# STCLock.net
KiCad netlist of a schematic drawn in Altium Designer
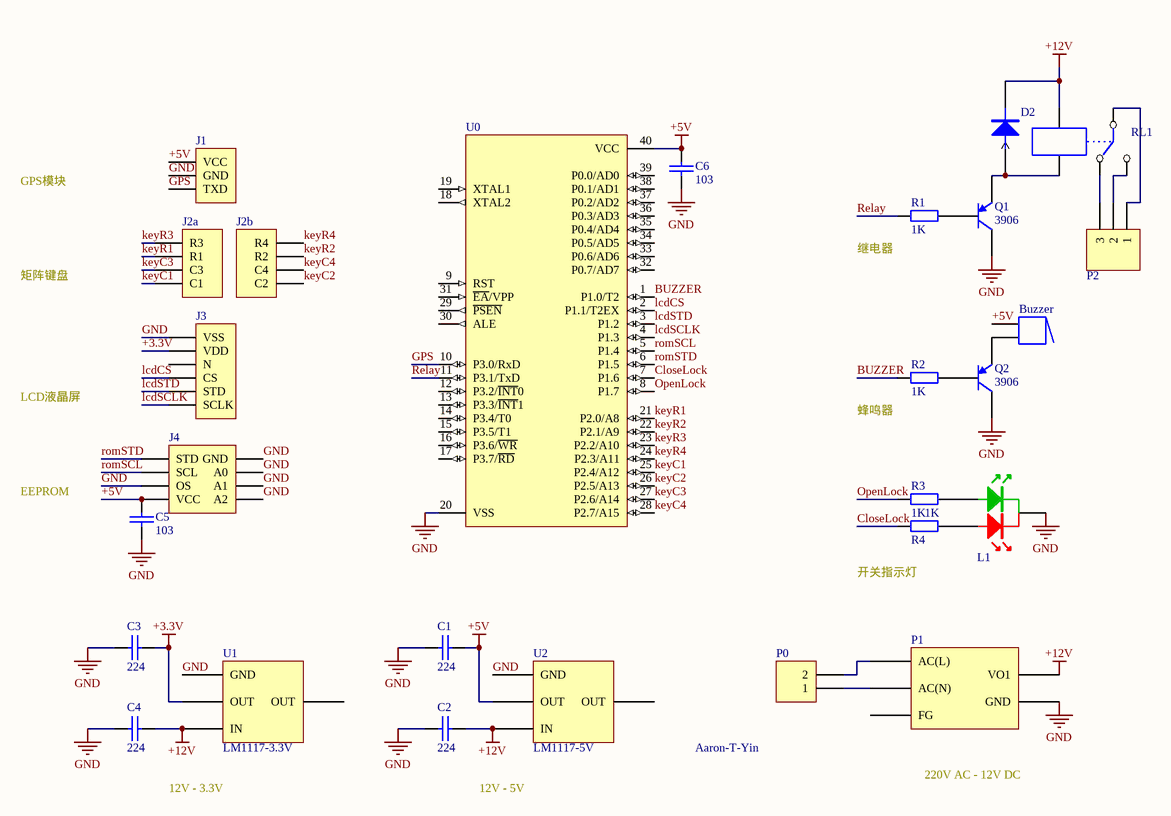
[diagram p0: STCLock.SchDoc]

(export (version "E")
  (design (tool "Eeschema 10.0.6"))
  (components
    (comp (ref "*") (value "AaronTYin") (libsource (lib "ET_SCHLIB") (part "AaronTYin")))
    (comp (ref "Buzzer")
      (value "Buzzer")
      (footprint "BUZ8/12")
      (description "Magnetic Transducer Buzzer")
      (fields (field (name "PUBLISHER") "Altium Limited"))
      (libsource (lib "Miscellaneous Devices") (part "Buzzer"))
    )
    (comp (ref "C1")
      (value "224")
      (footprint "0805")
      (description "Capacitor")
      (libsource (lib "ET_SCHLIB") (part "CAP"))
    )
    (comp (ref "C2")
      (value "224")
      (footprint "0805")
      (description "Capacitor")
      (libsource (lib "ET_SCHLIB") (part "CAP"))
    )
    (comp (ref "C3")
      (value "224")
      (footprint "0805")
      (description "Capacitor")
      (libsource (lib "ET_SCHLIB") (part "CAP"))
    )
    (comp (ref "C4")
      (value "224")
      (footprint "0805")
      (description "Capacitor")
      (libsource (lib "ET_SCHLIB") (part "CAP"))
    )
    (comp (ref "C5")
      (value "103")
      (footprint "0805")
      (description "Capacitor")
      (libsource (lib "ET_SCHLIB") (part "CAP"))
    )
    (comp (ref "C6")
      (value "103")
      (footprint "0805")
      (description "Capacitor")
      (libsource (lib "ET_SCHLIB") (part "CAP"))
    )
    (comp (ref "D2")
      (value "DIODE")
      (footprint "5819")
      (description "Diode")
      (libsource (lib "ET_SCHLIB") (part "DIODE"))
    )
    (comp (ref "J1")
      (value "GPS")
      (footprint "HDR1X3")
      (description "Header, 3-Pin")
      (fields (field (name "PUBLISHER") "Altium Limited"))
      (libsource (lib "") (part "Header 3_1"))
    )
    (comp (ref "J2a")
      (value "Header 4")
      (footprint "HDR1X4")
      (description "Header, 4-Pin")
      (fields (field (name "PUBLISHER") "Altium Limited"))
      (libsource (lib "Miscellaneous Connectors") (part "Header 4"))
    )
    (comp (ref "J2b")
      (value "Header 4")
      (footprint "HDR1X4")
      (description "Header, 4-Pin")
      (fields (field (name "PUBLISHER") "Altium Limited"))
      (libsource (lib "") (part "Header 4_1"))
    )
    (comp (ref "J3")
      (value "LCD12864")
      (footprint "HDR1X6")
      (description "Header, 6-Pin")
      (fields (field (name "PUBLISHER") "Altium Limited"))
      (libsource (lib "Miscellaneous Connectors") (part "Header 6"))
    )
    (comp (ref "J4") (value "AT24C02") (footprint "DIP8") (libsource (lib "ET_SCHLIB") (part "LM75A")))
    (comp (ref "L1") (value "LED_3_K") (footprint "HDR1X3") (libsource (lib "ET_SCHLIB") (part "LED_3_K")))
    (comp (ref "P0")
      (value "Header 2")
      (footprint "DG46G_2")
      (description "Header, 2-Pin")
      (fields (field (name "PUBLISHER") "Altium Limited"))
      (libsource (lib "Miscellaneous Connectors") (part "Header 2"))
    )
    (comp (ref "P1")
      (value "LAP5-220SXX")
      (footprint "LAP5-220SXX")
      (libsource (lib "ET_SCHLIB") (part "LAP5-220SXX"))
    )
    (comp (ref "P2")
      (value "Header 3")
      (footprint "111")
      (description "Header, 3-Pin")
      (fields (field (name "PUBLISHER") "Altium Limited"))
      (libsource (lib "Miscellaneous Connectors") (part "Header 3"))
    )
    (comp (ref "Q1")
      (value "3906")
      (footprint "SOT-23-et")
      (description "PNP General Purpose Amplifier")
      (fields (field (name "PUBLISHER") "Altium Limited"))
      (libsource (lib "Miscellaneous Devices") (part "2N3906"))
    )
    (comp (ref "Q2")
      (value "3906")
      (footprint "SOT-23-et")
      (description "PNP General Purpose Amplifier")
      (fields (field (name "PUBLISHER") "Altium Limited"))
      (libsource (lib "Miscellaneous Devices") (part "2N3906"))
    )
    (comp (ref "R1")
      (value "1K")
      (footprint "0805")
      (description "Semiconductor Resistor")
      (fields (field (name "Comment") "Res Semi") (field (name "PUBLISHER") "Altium Limited"))
      (libsource (lib "Miscellaneous Devices") (part "Res Semi"))
    )
    (comp (ref "R2")
      (value "1K")
      (footprint "0805")
      (description "Semiconductor Resistor")
      (fields (field (name "Comment") "Res Semi") (field (name "PUBLISHER") "Altium Limited"))
      (libsource (lib "Miscellaneous Devices") (part "Res Semi"))
    )
    (comp (ref "R3")
      (value "1K")
      (footprint "0805")
      (description "Resistor")
      (fields (field (name "Comment") "Res2") (field (name "PUBLISHER") "Altium Limited"))
      (libsource (lib "Miscellaneous Devices") (part "Res2"))
    )
    (comp (ref "R4")
      (value "1K")
      (footprint "0805")
      (description "Resistor")
      (fields (field (name "Comment") "Res2") (field (name "PUBLISHER") "Altium Limited"))
      (libsource (lib "Miscellaneous Devices") (part "Res2"))
    )
    (comp (ref "RL1") (value "G2R-1") (footprint "G2R-1") (libsource (lib "ET_SCHLIB") (part "G2R-1")))
    (comp (ref "U0")
      (value "STC89C52RC")
      (footprint "SOT129-1")
      (description "80C51 8-Bit Flash Microcontroller Family, 4 kB Flash")
      (fields (field (name "PUBLISHER") "Altium Limited"))
      (libsource (lib "Philips Microcontroller 8-Bit") (part "P89C51X2BN"))
    )
    (comp (ref "U1")
      (value "LM1117-3.3V")
      (footprint "AMS1117")
      (libsource (lib "ET_SCHLIB") (part "LM1117"))
    )
    (comp (ref "U2") (value "LM1117-5V") (footprint "AMS1117") (libsource (lib "ET_SCHLIB") (part "LM1117")))
  )
  (nets
    (net (code "1") (name "+3.3V") (class "Default")
      (node (ref "C3") (pin "2") (pintype "passive"))
      (node (ref "J3") (pin "2") (pinfunction "VDD_2") (pintype "passive"))
      (node (ref "U1") (pin "2") (pinfunction "OUT_2") (pintype "passive"))
    )
    (net (code "2") (name "+5V") (class "Default")
      (node (ref "Buzzer") (pin "1") (pinfunction "1_1") (pintype "passive"))
      (node (ref "C1") (pin "2") (pintype "passive"))
      (node (ref "C5") (pin "1") (pintype "passive"))
      (node (ref "C6") (pin "1") (pintype "passive"))
      (node (ref "J1") (pin "1") (pinfunction "VCC_1") (pintype "passive"))
      (node (ref "J4") (pin "4") (pinfunction "VCC_4") (pintype "passive"))
      (node (ref "U0") (pin "40") (pinfunction "VCC_40") (pintype "power_in"))
      (node (ref "U2") (pin "2") (pinfunction "OUT_2") (pintype "passive"))
    )
    (net (code "3") (name "+12V") (class "Default")
      (node (ref "C2") (pin "2") (pintype "passive"))
      (node (ref "C4") (pin "2") (pintype "passive"))
      (node (ref "D2") (pin "2") (pintype "passive"))
      (node (ref "P1") (pin "4") (pinfunction "VO1_4") (pintype "passive"))
      (node (ref "RL1") (pin "5") (pintype "passive"))
      (node (ref "U1") (pin "3") (pinfunction "IN_3") (pintype "passive"))
      (node (ref "U2") (pin "3") (pinfunction "IN_3") (pintype "passive"))
    )
    (net (code "4") (name "/BUZZER") (class "Default")
      (node (ref "R2") (pin "1") (pinfunction "1_1") (pintype "passive"))
      (node (ref "U0") (pin "1") (pinfunction "P1.0/T2_1") (pintype "bidirectional"))
    )
    (net (code "5") (name "/CloseLock") (class "Default")
      (node (ref "R4") (pin "1") (pinfunction "1_1") (pintype "passive"))
      (node (ref "U0") (pin "7") (pinfunction "P1.6_7") (pintype "bidirectional"))
    )
    (net (code "6") (name "/GPS") (class "Default")
      (node (ref "J1") (pin "3") (pinfunction "TXD_3") (pintype "passive"))
      (node (ref "U0") (pin "10") (pinfunction "P3.0/RxD_10") (pintype "bidirectional"))
    )
    (net (code "7") (name "/OpenLock") (class "Default")
      (node (ref "R3") (pin "1") (pinfunction "1_1") (pintype "passive"))
      (node (ref "U0") (pin "8") (pinfunction "P1.7_8") (pintype "bidirectional"))
    )
    (net (code "8") (name "/Relay") (class "Default")
      (node (ref "R1") (pin "1") (pinfunction "1_1") (pintype "passive"))
      (node (ref "U0") (pin "11") (pinfunction "P3.1/TxD_11") (pintype "bidirectional"))
    )
    (net (code "9") (name "/keyC1") (class "Default")
      (node (ref "J2a") (pin "4") (pinfunction "C1_4") (pintype "passive"))
      (node (ref "U0") (pin "25") (pinfunction "P2.4/A12_25") (pintype "bidirectional"))
    )
    (net (code "10") (name "/keyC2") (class "Default")
      (node (ref "J2b") (pin "1") (pinfunction "C2_1") (pintype "passive"))
      (node (ref "U0") (pin "26") (pinfunction "P2.5/A13_26") (pintype "bidirectional"))
    )
    (net (code "11") (name "/keyC3") (class "Default")
      (node (ref "J2a") (pin "3") (pinfunction "C3_3") (pintype "passive"))
      (node (ref "U0") (pin "27") (pinfunction "P2.6/A14_27") (pintype "bidirectional"))
    )
    (net (code "12") (name "/keyC4") (class "Default")
      (node (ref "J2b") (pin "2") (pinfunction "C4_2") (pintype "passive"))
      (node (ref "U0") (pin "28") (pinfunction "P2.7/A15_28") (pintype "bidirectional"))
    )
    (net (code "13") (name "/keyR1") (class "Default")
      (node (ref "J2a") (pin "2") (pinfunction "R1_2") (pintype "passive"))
      (node (ref "U0") (pin "21") (pinfunction "P2.0/A8_21") (pintype "bidirectional"))
    )
    (net (code "14") (name "/keyR2") (class "Default")
      (node (ref "J2b") (pin "3") (pinfunction "R2_3") (pintype "passive"))
      (node (ref "U0") (pin "22") (pinfunction "P2.1/A9_22") (pintype "bidirectional"))
    )
    (net (code "15") (name "/keyR3") (class "Default")
      (node (ref "J2a") (pin "1") (pinfunction "R3_1") (pintype "passive"))
      (node (ref "U0") (pin "23") (pinfunction "P2.2/A10_23") (pintype "bidirectional"))
    )
    (net (code "16") (name "/keyR4") (class "Default")
      (node (ref "J2b") (pin "4") (pinfunction "R4_4") (pintype "passive"))
      (node (ref "U0") (pin "24") (pinfunction "P2.3/A11_24") (pintype "bidirectional"))
    )
    (net (code "17") (name "/lcdCS") (class "Default")
      (node (ref "J3") (pin "4") (pinfunction "CS_4") (pintype "passive"))
      (node (ref "U0") (pin "2") (pinfunction "P1.1/T2EX_2") (pintype "bidirectional"))
    )
    (net (code "18") (name "/lcdSCLK") (class "Default")
      (node (ref "J3") (pin "6") (pinfunction "SCLK_6") (pintype "passive"))
      (node (ref "U0") (pin "4") (pinfunction "P1.3_4") (pintype "bidirectional"))
    )
    (net (code "19") (name "/lcdSTD") (class "Default")
      (node (ref "J3") (pin "5") (pinfunction "STD_5") (pintype "passive"))
      (node (ref "U0") (pin "3") (pinfunction "P1.2_3") (pintype "bidirectional"))
    )
    (net (code "20") (name "/romSCL") (class "Default")
      (node (ref "J4") (pin "2") (pinfunction "SCL_2") (pintype "passive"))
      (node (ref "U0") (pin "5") (pinfunction "P1.4_5") (pintype "bidirectional"))
    )
    (net (code "21") (name "/romSTD") (class "Default")
      (node (ref "J4") (pin "1") (pinfunction "STD_1") (pintype "passive"))
      (node (ref "U0") (pin "6") (pinfunction "P1.5_6") (pintype "bidirectional"))
    )
    (net (code "22") (name "GND") (class "Default")
      (node (ref "C1") (pin "1") (pintype "passive"))
      (node (ref "C2") (pin "1") (pintype "passive"))
      (node (ref "C3") (pin "1") (pintype "passive"))
      (node (ref "C4") (pin "1") (pintype "passive"))
      (node (ref "C5") (pin "2") (pintype "passive"))
      (node (ref "C6") (pin "2") (pintype "passive"))
      (node (ref "J1") (pin "2") (pinfunction "GND_2") (pintype "passive"))
      (node (ref "J3") (pin "1") (pinfunction "VSS_1") (pintype "passive"))
      (node (ref "J4") (pin "3") (pinfunction "OS_3") (pintype "passive"))
      (node (ref "J4") (pin "5") (pinfunction "A2_5") (pintype "passive"))
      (node (ref "J4") (pin "6") (pinfunction "A1_6") (pintype "passive"))
      (node (ref "J4") (pin "7") (pinfunction "A0_7") (pintype "passive"))
      (node (ref "J4") (pin "8") (pinfunction "GND_8") (pintype "passive"))
      (node (ref "L1") (pin "1") (pintype "passive"))
      (node (ref "P1") (pin "5") (pinfunction "GND_5") (pintype "passive"))
      (node (ref "Q1") (pin "3") (pinfunction "C_3") (pintype "passive"))
      (node (ref "Q2") (pin "3") (pinfunction "C_3") (pintype "passive"))
      (node (ref "U0") (pin "20") (pinfunction "VSS_20") (pintype "power_in"))
      (node (ref "U1") (pin "1") (pinfunction "GND_1") (pintype "passive"))
      (node (ref "U2") (pin "1") (pinfunction "GND_1") (pintype "passive"))
    )
    (net (code "23") (name "Net-(L1-Pad2)") (class "Default")
      (node (ref "L1") (pin "2") (pintype "passive"))
      (node (ref "R4") (pin "2") (pinfunction "2_2") (pintype "passive"))
    )
    (net (code "24") (name "Net-(L1-Pad3)") (class "Default")
      (node (ref "L1") (pin "3") (pintype "passive"))
      (node (ref "R3") (pin "2") (pinfunction "2_2") (pintype "passive"))
    )
    (net (code "25") (name "Net-(P1-AC(L))") (class "Default")
      (node (ref "P0") (pin "2") (pinfunction "2_2") (pintype "passive"))
      (node (ref "P1") (pin "3") (pinfunction "AC(L)_3") (pintype "passive"))
    )
    (net (code "26") (name "Net-(P1-AC(N))") (class "Default")
      (node (ref "P0") (pin "1") (pinfunction "1_1") (pintype "passive"))
      (node (ref "P1") (pin "2") (pinfunction "AC(N)_2") (pintype "passive"))
    )
    (net (code "27") (name "Net-(P2-Pad1)") (class "Default")
      (node (ref "P2") (pin "1") (pinfunction "1_1") (pintype "passive"))
      (node (ref "RL1") (pin "4") (pintype "passive"))
    )
    (net (code "28") (name "Net-(P2-Pad2)") (class "Default")
      (node (ref "P2") (pin "2") (pinfunction "2_2") (pintype "passive"))
      (node (ref "RL1") (pin "3") (pintype "passive"))
    )
    (net (code "29") (name "Net-(P2-Pad3)") (class "Default")
      (node (ref "P2") (pin "3") (pinfunction "3_3") (pintype "passive"))
      (node (ref "RL1") (pin "2") (pintype "passive"))
    )
    (net (code "30") (name "Net-(Q1-B)") (class "Default")
      (node (ref "Q1") (pin "2") (pinfunction "B_2") (pintype "passive"))
      (node (ref "R1") (pin "2") (pinfunction "2_2") (pintype "passive"))
    )
    (net (code "31") (name "Net-(Q1-E)") (class "Default")
      (node (ref "D2") (pin "1") (pintype "passive"))
      (node (ref "Q1") (pin "1") (pinfunction "E_1") (pintype "passive"))
      (node (ref "RL1") (pin "1") (pintype "passive"))
    )
    (net (code "32") (name "Net-(Q2-B)") (class "Default")
      (node (ref "Q2") (pin "2") (pinfunction "B_2") (pintype "passive"))
      (node (ref "R2") (pin "2") (pinfunction "2_2") (pintype "passive"))
    )
    (net (code "33") (name "Net-(Q2-E)") (class "Default")
      (node (ref "Buzzer") (pin "2") (pinfunction "2_2") (pintype "passive"))
      (node (ref "Q2") (pin "1") (pinfunction "E_1") (pintype "passive"))
    )
    (net (code "34") (name "unconnected-(J3-N-Pad3)") (class "Default")
      (node (ref "J3") (pin "3") (pinfunction "N_3") (pintype "passive"))
    )
    (net (code "35") (name "unconnected-(P1-FG-Pad1)") (class "Default")
      (node (ref "P1") (pin "1") (pinfunction "FG_1") (pintype "passive"))
    )
    (net (code "36") (name "unconnected-(U0-ALE-Pad30)") (class "Default")
      (node (ref "U0") (pin "30") (pinfunction "ALE_30") (pintype "output"))
    )
    (net (code "37") (name "unconnected-(U0-P0.0{slash}AD0-Pad39)") (class "Default")
      (node (ref "U0") (pin "39") (pinfunction "P0.0/AD0_39") (pintype "bidirectional"))
    )
    (net (code "38") (name "unconnected-(U0-P0.1{slash}AD1-Pad38)") (class "Default")
      (node (ref "U0") (pin "38") (pinfunction "P0.1/AD1_38") (pintype "bidirectional"))
    )
    (net (code "39") (name "unconnected-(U0-P0.2{slash}AD2-Pad37)") (class "Default")
      (node (ref "U0") (pin "37") (pinfunction "P0.2/AD2_37") (pintype "bidirectional"))
    )
    (net (code "40") (name "unconnected-(U0-P0.3{slash}AD3-Pad36)") (class "Default")
      (node (ref "U0") (pin "36") (pinfunction "P0.3/AD3_36") (pintype "bidirectional"))
    )
    (net (code "41") (name "unconnected-(U0-P0.4{slash}AD4-Pad35)") (class "Default")
      (node (ref "U0") (pin "35") (pinfunction "P0.4/AD4_35") (pintype "bidirectional"))
    )
    (net (code "42") (name "unconnected-(U0-P0.5{slash}AD5-Pad34)") (class "Default")
      (node (ref "U0") (pin "34") (pinfunction "P0.5/AD5_34") (pintype "bidirectional"))
    )
    (net (code "43") (name "unconnected-(U0-P0.6{slash}AD6-Pad33)") (class "Default")
      (node (ref "U0") (pin "33") (pinfunction "P0.6/AD6_33") (pintype "bidirectional"))
    )
    (net (code "44") (name "unconnected-(U0-P0.7{slash}AD7-Pad32)") (class "Default")
      (node (ref "U0") (pin "32") (pinfunction "P0.7/AD7_32") (pintype "bidirectional"))
    )
    (net (code "45") (name "unconnected-(U0-P3.2{slash}~{INT}0-Pad12)") (class "Default")
      (node (ref "U0") (pin "12") (pinfunction "P3.2/~{INT}0_12") (pintype "bidirectional"))
    )
    (net (code "46") (name "unconnected-(U0-P3.3{slash}~{INT}1-Pad13)") (class "Default")
      (node (ref "U0") (pin "13") (pinfunction "P3.3/~{INT}1_13") (pintype "bidirectional"))
    )
    (net (code "47") (name "unconnected-(U0-P3.4{slash}T0-Pad14)") (class "Default")
      (node (ref "U0") (pin "14") (pinfunction "P3.4/T0_14") (pintype "bidirectional"))
    )
    (net (code "48") (name "unconnected-(U0-P3.5{slash}T1-Pad15)") (class "Default")
      (node (ref "U0") (pin "15") (pinfunction "P3.5/T1_15") (pintype "bidirectional"))
    )
    (net (code "49") (name "unconnected-(U0-P3.6{slash}~{WR}-Pad16)") (class "Default")
      (node (ref "U0") (pin "16") (pinfunction "P3.6/~{WR}_16") (pintype "bidirectional"))
    )
    (net (code "50") (name "unconnected-(U0-P3.7{slash}~{RD}-Pad17)") (class "Default")
      (node (ref "U0") (pin "17") (pinfunction "P3.7/~{RD}_17") (pintype "bidirectional"))
    )
    (net (code "51") (name "unconnected-(U0-RST-Pad9)") (class "Default")
      (node (ref "U0") (pin "9") (pinfunction "RST_9") (pintype "input"))
    )
    (net (code "52") (name "unconnected-(U0-XTAL1-Pad19)") (class "Default")
      (node (ref "U0") (pin "19") (pinfunction "XTAL1_19") (pintype "input"))
    )
    (net (code "53") (name "unconnected-(U0-XTAL2-Pad18)") (class "Default")
      (node (ref "U0") (pin "18") (pinfunction "XTAL2_18") (pintype "output"))
    )
    (net (code "54") (name "unconnected-(U0-~{EA}{slash}VPP-Pad31)") (class "Default")
      (node (ref "U0") (pin "31") (pinfunction "~{EA}/VPP_31") (pintype "input"))
    )
    (net (code "55") (name "unconnected-(U0-~{PSEN}-Pad29)") (class "Default")
      (node (ref "U0") (pin "29") (pinfunction "~{PSEN}_29") (pintype "output"))
    )
    (net (code "56") (name "unconnected-(U1-OUT-Pad4)") (class "Default")
      (node (ref "U1") (pin "4") (pinfunction "OUT_4") (pintype "passive"))
    )
    (net (code "57") (name "unconnected-(U2-OUT-Pad4)") (class "Default")
      (node (ref "U2") (pin "4") (pinfunction "OUT_4") (pintype "passive"))
    )
  )
)
